# love-flow-lamp.net
KiCad netlist of a schematic drawn in Altium Designer
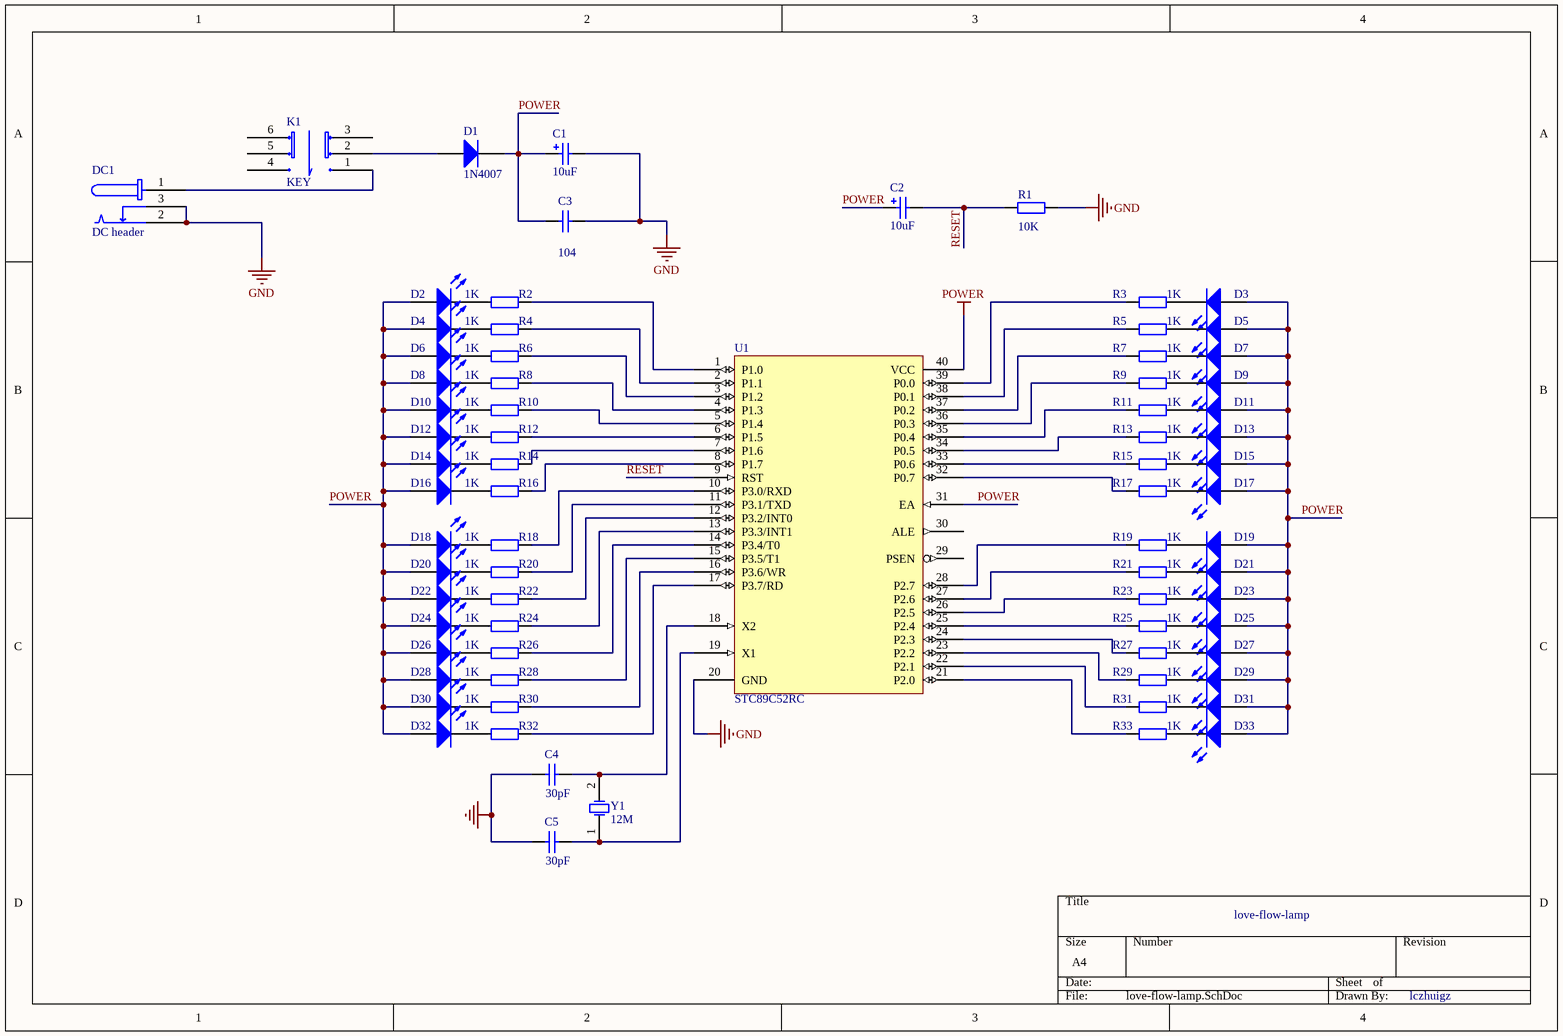
[diagram p0: love-flow-lamp.SchDoc]

(export (version "E")
  (design (tool "Eeschema 10.0.6"))
  (components
    (comp (ref "C1")
      (value "10uF")
      (footprint "RB1")
      (description "Polarized Capacitor (Radial)")
      (fields (field (name "Comment") "Cap Pol1") (field (name "PUBLISHER") "Altium Limited"))
      (libsource (lib "Schlib1") (part "Cap Pol1"))
    )
    (comp (ref "C2")
      (value "10uF")
      (footprint "RB1")
      (description "Polarized Capacitor (Radial)")
      (fields (field (name "Comment") "Cap Pol1") (field (name "PUBLISHER") "Altium Limited"))
      (libsource (lib "Schlib1") (part "Cap Pol1"))
    )
    (comp (ref "C3")
      (value "104")
      (footprint "RAD-0.1")
      (description "Capacitor")
      (fields (field (name "Comment") "Cap") (field (name "PUBLISHER") "Altium Limited"))
      (libsource (lib "Miscellaneous Devices") (part "Cap"))
    )
    (comp (ref "C4")
      (value "30pF")
      (footprint "RAD-0.1")
      (description "Capacitor")
      (fields (field (name "Comment") "Cap") (field (name "PUBLISHER") "Altium Limited"))
      (libsource (lib "Schlib1") (part "Cap"))
    )
    (comp (ref "C5")
      (value "30pF")
      (footprint "RAD-0.1")
      (description "Capacitor")
      (fields (field (name "Comment") "Cap") (field (name "PUBLISHER") "Altium Limited"))
      (libsource (lib "Schlib1") (part "Cap"))
    )
    (comp (ref "D1")
      (value "1N4007")
      (footprint "DIODE-0.4")
      (description "1 Amp General Purpose Rectifier")
      (fields (field (name "PUBLISHER") "Altium Limited"))
      (libsource (lib "Schlib1") (part "Diode 1N4007"))
    )
    (comp (ref "D2")
      (value "LED0")
      (footprint "LED")
      (description "Typical INFRARED GaAs LED")
      (fields (field (name "PUBLISHER") "Altium Limited"))
      (libsource (lib "Schlib1") (part "LED0"))
    )
    (comp (ref "D3")
      (value "LED0")
      (footprint "LED")
      (description "Typical INFRARED GaAs LED")
      (fields (field (name "PUBLISHER") "Altium Limited"))
      (libsource (lib "Schlib1") (part "LED0"))
    )
    (comp (ref "D4")
      (value "LED0")
      (footprint "LED")
      (description "Typical INFRARED GaAs LED")
      (fields (field (name "PUBLISHER") "Altium Limited"))
      (libsource (lib "Schlib1") (part "LED0"))
    )
    (comp (ref "D5")
      (value "LED0")
      (footprint "LED")
      (description "Typical INFRARED GaAs LED")
      (fields (field (name "PUBLISHER") "Altium Limited"))
      (libsource (lib "Schlib1") (part "LED0"))
    )
    (comp (ref "D6")
      (value "LED0")
      (footprint "LED")
      (description "Typical INFRARED GaAs LED")
      (fields (field (name "PUBLISHER") "Altium Limited"))
      (libsource (lib "Schlib1") (part "LED0"))
    )
    (comp (ref "D7")
      (value "LED0")
      (footprint "LED")
      (description "Typical INFRARED GaAs LED")
      (fields (field (name "PUBLISHER") "Altium Limited"))
      (libsource (lib "Schlib1") (part "LED0"))
    )
    (comp (ref "D8")
      (value "LED0")
      (footprint "LED")
      (description "Typical INFRARED GaAs LED")
      (fields (field (name "PUBLISHER") "Altium Limited"))
      (libsource (lib "Schlib1") (part "LED0"))
    )
    (comp (ref "D9")
      (value "LED0")
      (footprint "LED")
      (description "Typical INFRARED GaAs LED")
      (fields (field (name "PUBLISHER") "Altium Limited"))
      (libsource (lib "Schlib1") (part "LED0"))
    )
    (comp (ref "D10")
      (value "LED0")
      (footprint "LED")
      (description "Typical INFRARED GaAs LED")
      (fields (field (name "PUBLISHER") "Altium Limited"))
      (libsource (lib "Schlib1") (part "LED0"))
    )
    (comp (ref "D11")
      (value "LED0")
      (footprint "LED")
      (description "Typical INFRARED GaAs LED")
      (fields (field (name "PUBLISHER") "Altium Limited"))
      (libsource (lib "Schlib1") (part "LED0"))
    )
    (comp (ref "D12")
      (value "LED0")
      (footprint "LED")
      (description "Typical INFRARED GaAs LED")
      (fields (field (name "PUBLISHER") "Altium Limited"))
      (libsource (lib "Schlib1") (part "LED0"))
    )
    (comp (ref "D13")
      (value "LED0")
      (footprint "LED")
      (description "Typical INFRARED GaAs LED")
      (fields (field (name "PUBLISHER") "Altium Limited"))
      (libsource (lib "Schlib1") (part "LED0"))
    )
    (comp (ref "D14")
      (value "LED0")
      (footprint "LED")
      (description "Typical INFRARED GaAs LED")
      (fields (field (name "PUBLISHER") "Altium Limited"))
      (libsource (lib "Schlib1") (part "LED0"))
    )
    (comp (ref "D15")
      (value "LED0")
      (footprint "LED")
      (description "Typical INFRARED GaAs LED")
      (fields (field (name "PUBLISHER") "Altium Limited"))
      (libsource (lib "Schlib1") (part "LED0"))
    )
    (comp (ref "D16")
      (value "LED0")
      (footprint "LED")
      (description "Typical INFRARED GaAs LED")
      (fields (field (name "PUBLISHER") "Altium Limited"))
      (libsource (lib "Schlib1") (part "LED0"))
    )
    (comp (ref "D17")
      (value "LED0")
      (footprint "LED")
      (description "Typical INFRARED GaAs LED")
      (fields (field (name "PUBLISHER") "Altium Limited"))
      (libsource (lib "Schlib1") (part "LED0"))
    )
    (comp (ref "D18")
      (value "LED0")
      (footprint "LED")
      (description "Typical INFRARED GaAs LED")
      (fields (field (name "PUBLISHER") "Altium Limited"))
      (libsource (lib "Schlib1") (part "LED0"))
    )
    (comp (ref "D19")
      (value "LED0")
      (footprint "LED")
      (description "Typical INFRARED GaAs LED")
      (fields (field (name "PUBLISHER") "Altium Limited"))
      (libsource (lib "Schlib1") (part "LED0"))
    )
    (comp (ref "D20")
      (value "LED0")
      (footprint "LED")
      (description "Typical INFRARED GaAs LED")
      (fields (field (name "PUBLISHER") "Altium Limited"))
      (libsource (lib "Schlib1") (part "LED0"))
    )
    (comp (ref "D21")
      (value "LED0")
      (footprint "LED")
      (description "Typical INFRARED GaAs LED")
      (fields (field (name "PUBLISHER") "Altium Limited"))
      (libsource (lib "Schlib1") (part "LED0"))
    )
    (comp (ref "D22")
      (value "LED0")
      (footprint "LED")
      (description "Typical INFRARED GaAs LED")
      (fields (field (name "PUBLISHER") "Altium Limited"))
      (libsource (lib "Schlib1") (part "LED0"))
    )
    (comp (ref "D23")
      (value "LED0")
      (footprint "LED")
      (description "Typical INFRARED GaAs LED")
      (fields (field (name "PUBLISHER") "Altium Limited"))
      (libsource (lib "Schlib1") (part "LED0"))
    )
    (comp (ref "D24")
      (value "LED0")
      (footprint "LED")
      (description "Typical INFRARED GaAs LED")
      (fields (field (name "PUBLISHER") "Altium Limited"))
      (libsource (lib "Schlib1") (part "LED0"))
    )
    (comp (ref "D25")
      (value "LED0")
      (footprint "LED")
      (description "Typical INFRARED GaAs LED")
      (fields (field (name "PUBLISHER") "Altium Limited"))
      (libsource (lib "Schlib1") (part "LED0"))
    )
    (comp (ref "D26")
      (value "LED0")
      (footprint "LED")
      (description "Typical INFRARED GaAs LED")
      (fields (field (name "PUBLISHER") "Altium Limited"))
      (libsource (lib "Schlib1") (part "LED0"))
    )
    (comp (ref "D27")
      (value "LED0")
      (footprint "LED")
      (description "Typical INFRARED GaAs LED")
      (fields (field (name "PUBLISHER") "Altium Limited"))
      (libsource (lib "Schlib1") (part "LED0"))
    )
    (comp (ref "D28")
      (value "LED0")
      (footprint "LED")
      (description "Typical INFRARED GaAs LED")
      (fields (field (name "PUBLISHER") "Altium Limited"))
      (libsource (lib "Schlib1") (part "LED0"))
    )
    (comp (ref "D29")
      (value "LED0")
      (footprint "LED")
      (description "Typical INFRARED GaAs LED")
      (fields (field (name "PUBLISHER") "Altium Limited"))
      (libsource (lib "Schlib1") (part "LED0"))
    )
    (comp (ref "D30")
      (value "LED0")
      (footprint "LED")
      (description "Typical INFRARED GaAs LED")
      (fields (field (name "PUBLISHER") "Altium Limited"))
      (libsource (lib "Schlib1") (part "LED0"))
    )
    (comp (ref "D31")
      (value "LED0")
      (footprint "LED")
      (description "Typical INFRARED GaAs LED")
      (fields (field (name "PUBLISHER") "Altium Limited"))
      (libsource (lib "Schlib1") (part "LED0"))
    )
    (comp (ref "D32")
      (value "LED0")
      (footprint "LED")
      (description "Typical INFRARED GaAs LED")
      (fields (field (name "PUBLISHER") "Altium Limited"))
      (libsource (lib "Schlib1") (part "LED0"))
    )
    (comp (ref "D33")
      (value "LED0")
      (footprint "LED")
      (description "Typical INFRARED GaAs LED")
      (fields (field (name "PUBLISHER") "Altium Limited"))
      (libsource (lib "Schlib1") (part "LED0"))
    )
    (comp (ref "DC1") (value "DC header") (footprint "DC") (libsource (lib "love-flow-lamp") (part "DC")))
    (comp (ref "K1") (value "KEY") (footprint "KEY-6") (libsource (lib "love-flow-lamp") (part "KEY")))
    (comp (ref "R1")
      (value "10K")
      (footprint "AXIAL-0.3")
      (description "Resistor")
      (fields (field (name "Comment") "Res2") (field (name "PUBLISHER") "Altium Limited"))
      (libsource (lib "Schlib1") (part "Res2"))
    )
    (comp (ref "R2")
      (value "1K")
      (footprint "AXIAL-0.3")
      (description "Resistor")
      (fields (field (name "Comment") "Res2") (field (name "PUBLISHER") "Altium Limited"))
      (libsource (lib "Schlib1") (part "Res2"))
    )
    (comp (ref "R3")
      (value "1K")
      (footprint "AXIAL-0.3")
      (description "Resistor")
      (fields (field (name "Comment") "Res2") (field (name "PUBLISHER") "Altium Limited"))
      (libsource (lib "Schlib1") (part "Res2"))
    )
    (comp (ref "R4")
      (value "1K")
      (footprint "AXIAL-0.3")
      (description "Resistor")
      (fields (field (name "Comment") "Res2") (field (name "PUBLISHER") "Altium Limited"))
      (libsource (lib "Schlib1") (part "Res2"))
    )
    (comp (ref "R5")
      (value "1K")
      (footprint "AXIAL-0.3")
      (description "Resistor")
      (fields (field (name "Comment") "Res2") (field (name "PUBLISHER") "Altium Limited"))
      (libsource (lib "Schlib1") (part "Res2"))
    )
    (comp (ref "R6")
      (value "1K")
      (footprint "AXIAL-0.3")
      (description "Resistor")
      (fields (field (name "Comment") "Res2") (field (name "PUBLISHER") "Altium Limited"))
      (libsource (lib "Schlib1") (part "Res2"))
    )
    (comp (ref "R7")
      (value "1K")
      (footprint "AXIAL-0.3")
      (description "Resistor")
      (fields (field (name "Comment") "Res2") (field (name "PUBLISHER") "Altium Limited"))
      (libsource (lib "Schlib1") (part "Res2"))
    )
    (comp (ref "R8")
      (value "1K")
      (footprint "AXIAL-0.3")
      (description "Resistor")
      (fields (field (name "Comment") "Res2") (field (name "PUBLISHER") "Altium Limited"))
      (libsource (lib "Schlib1") (part "Res2"))
    )
    (comp (ref "R9")
      (value "1K")
      (footprint "AXIAL-0.3")
      (description "Resistor")
      (fields (field (name "Comment") "Res2") (field (name "PUBLISHER") "Altium Limited"))
      (libsource (lib "Schlib1") (part "Res2"))
    )
    (comp (ref "R10")
      (value "1K")
      (footprint "AXIAL-0.3")
      (description "Resistor")
      (fields (field (name "Comment") "Res2") (field (name "PUBLISHER") "Altium Limited"))
      (libsource (lib "Schlib1") (part "Res2"))
    )
    (comp (ref "R11")
      (value "1K")
      (footprint "AXIAL-0.3")
      (description "Resistor")
      (fields (field (name "Comment") "Res2") (field (name "PUBLISHER") "Altium Limited"))
      (libsource (lib "Schlib1") (part "Res2"))
    )
    (comp (ref "R12")
      (value "1K")
      (footprint "AXIAL-0.3")
      (description "Resistor")
      (fields (field (name "Comment") "Res2") (field (name "PUBLISHER") "Altium Limited"))
      (libsource (lib "Schlib1") (part "Res2"))
    )
    (comp (ref "R13")
      (value "1K")
      (footprint "AXIAL-0.3")
      (description "Resistor")
      (fields (field (name "Comment") "Res2") (field (name "PUBLISHER") "Altium Limited"))
      (libsource (lib "Schlib1") (part "Res2"))
    )
    (comp (ref "R14")
      (value "1K")
      (footprint "AXIAL-0.3")
      (description "Resistor")
      (fields (field (name "Comment") "Res2") (field (name "PUBLISHER") "Altium Limited"))
      (libsource (lib "Schlib1") (part "Res2"))
    )
    (comp (ref "R15")
      (value "1K")
      (footprint "AXIAL-0.3")
      (description "Resistor")
      (fields (field (name "Comment") "Res2") (field (name "PUBLISHER") "Altium Limited"))
      (libsource (lib "Schlib1") (part "Res2"))
    )
    (comp (ref "R16")
      (value "1K")
      (footprint "AXIAL-0.3")
      (description "Resistor")
      (fields (field (name "Comment") "Res2") (field (name "PUBLISHER") "Altium Limited"))
      (libsource (lib "Schlib1") (part "Res2"))
    )
    (comp (ref "R17")
      (value "1K")
      (footprint "AXIAL-0.3")
      (description "Resistor")
      (fields (field (name "Comment") "Res2") (field (name "PUBLISHER") "Altium Limited"))
      (libsource (lib "Schlib1") (part "Res2"))
    )
    (comp (ref "R18")
      (value "1K")
      (footprint "AXIAL-0.3")
      (description "Resistor")
      (fields (field (name "Comment") "Res2") (field (name "PUBLISHER") "Altium Limited"))
      (libsource (lib "Schlib1") (part "Res2"))
    )
    (comp (ref "R19")
      (value "1K")
      (footprint "AXIAL-0.3")
      (description "Resistor")
      (fields (field (name "Comment") "Res2") (field (name "PUBLISHER") "Altium Limited"))
      (libsource (lib "Schlib1") (part "Res2"))
    )
    (comp (ref "R20")
      (value "1K")
      (footprint "AXIAL-0.3")
      (description "Resistor")
      (fields (field (name "Comment") "Res2") (field (name "PUBLISHER") "Altium Limited"))
      (libsource (lib "Schlib1") (part "Res2"))
    )
    (comp (ref "R21")
      (value "1K")
      (footprint "AXIAL-0.3")
      (description "Resistor")
      (fields (field (name "Comment") "Res2") (field (name "PUBLISHER") "Altium Limited"))
      (libsource (lib "Schlib1") (part "Res2"))
    )
    (comp (ref "R22")
      (value "1K")
      (footprint "AXIAL-0.3")
      (description "Resistor")
      (fields (field (name "Comment") "Res2") (field (name "PUBLISHER") "Altium Limited"))
      (libsource (lib "Schlib1") (part "Res2"))
    )
    (comp (ref "R23")
      (value "1K")
      (footprint "AXIAL-0.3")
      (description "Resistor")
      (fields (field (name "Comment") "Res2") (field (name "PUBLISHER") "Altium Limited"))
      (libsource (lib "Schlib1") (part "Res2"))
    )
    (comp (ref "R24")
      (value "1K")
      (footprint "AXIAL-0.3")
      (description "Resistor")
      (fields (field (name "Comment") "Res2") (field (name "PUBLISHER") "Altium Limited"))
      (libsource (lib "Schlib1") (part "Res2"))
    )
    (comp (ref "R25")
      (value "1K")
      (footprint "AXIAL-0.3")
      (description "Resistor")
      (fields (field (name "Comment") "Res2") (field (name "PUBLISHER") "Altium Limited"))
      (libsource (lib "Schlib1") (part "Res2"))
    )
    (comp (ref "R26")
      (value "1K")
      (footprint "AXIAL-0.3")
      (description "Resistor")
      (fields (field (name "Comment") "Res2") (field (name "PUBLISHER") "Altium Limited"))
      (libsource (lib "Schlib1") (part "Res2"))
    )
    (comp (ref "R27")
      (value "1K")
      (footprint "AXIAL-0.3")
      (description "Resistor")
      (fields (field (name "Comment") "Res2") (field (name "PUBLISHER") "Altium Limited"))
      (libsource (lib "Schlib1") (part "Res2"))
    )
    (comp (ref "R28")
      (value "1K")
      (footprint "AXIAL-0.3")
      (description "Resistor")
      (fields (field (name "Comment") "Res2") (field (name "PUBLISHER") "Altium Limited"))
      (libsource (lib "Schlib1") (part "Res2"))
    )
    (comp (ref "R29")
      (value "1K")
      (footprint "AXIAL-0.3")
      (description "Resistor")
      (fields (field (name "Comment") "Res2") (field (name "PUBLISHER") "Altium Limited"))
      (libsource (lib "Schlib1") (part "Res2"))
    )
    (comp (ref "R30")
      (value "1K")
      (footprint "AXIAL-0.3")
      (description "Resistor")
      (fields (field (name "Comment") "Res2") (field (name "PUBLISHER") "Altium Limited"))
      (libsource (lib "Schlib1") (part "Res2"))
    )
    (comp (ref "R31")
      (value "1K")
      (footprint "AXIAL-0.3")
      (description "Resistor")
      (fields (field (name "Comment") "Res2") (field (name "PUBLISHER") "Altium Limited"))
      (libsource (lib "Schlib1") (part "Res2"))
    )
    (comp (ref "R32")
      (value "1K")
      (footprint "AXIAL-0.3")
      (description "Resistor")
      (fields (field (name "Comment") "Res2") (field (name "PUBLISHER") "Altium Limited"))
      (libsource (lib "Schlib1") (part "Res2"))
    )
    (comp (ref "R33")
      (value "1K")
      (footprint "AXIAL-0.3")
      (description "Resistor")
      (fields (field (name "Comment") "Res2") (field (name "PUBLISHER") "Altium Limited"))
      (libsource (lib "Schlib1") (part "Res2"))
    )
    (comp (ref "U1")
      (value "STC89C52RC")
      (footprint "PDIP-40")
      (libsource (lib "Schlib1") (part "STC89C52RC"))
    )
    (comp (ref "Y1")
      (value "12M")
      (footprint "BCY-W2/E4.7")
      (description "Crystal Oscillator")
      (fields (field (name "PUBLISHER") "Altium Limited"))
      (libsource (lib "Schlib1") (part "XTAL"))
    )
  )
  (nets
    (net (code "1") (name "/RESET") (class "Default")
      (node (ref "C2") (pin "2") (pinfunction "2_2") (pintype "passive"))
      (node (ref "R1") (pin "1") (pinfunction "1_1") (pintype "passive"))
      (node (ref "U1") (pin "9") (pinfunction "RST_9") (pintype "input"))
    )
    (net (code "2") (name "GND") (class "Default")
      (node (ref "C1") (pin "2") (pinfunction "2_2") (pintype "passive"))
      (node (ref "C3") (pin "2") (pinfunction "2_2") (pintype "passive"))
      (node (ref "C4") (pin "1") (pinfunction "1_1") (pintype "passive"))
      (node (ref "C5") (pin "1") (pinfunction "1_1") (pintype "passive"))
      (node (ref "DC1") (pin "2") (pinfunction "2_2") (pintype "passive"))
      (node (ref "DC1") (pin "3") (pinfunction "3_3") (pintype "passive"))
      (node (ref "R1") (pin "2") (pinfunction "2_2") (pintype "passive"))
      (node (ref "U1") (pin "20") (pinfunction "GND_20") (pintype "power_in"))
    )
    (net (code "3") (name "Net-(D1-A)") (class "Default")
      (node (ref "D1") (pin "1") (pinfunction "A_1") (pintype "passive"))
      (node (ref "K1") (pin "2") (pinfunction "2_2") (pintype "passive"))
    )
    (net (code "4") (name "Net-(D2-K)") (class "Default")
      (node (ref "D2") (pin "2") (pinfunction "K_2") (pintype "passive"))
      (node (ref "R2") (pin "1") (pinfunction "1_1") (pintype "passive"))
    )
    (net (code "5") (name "Net-(D3-K)") (class "Default")
      (node (ref "D3") (pin "2") (pinfunction "K_2") (pintype "passive"))
      (node (ref "R3") (pin "2") (pinfunction "2_2") (pintype "passive"))
    )
    (net (code "6") (name "Net-(D4-K)") (class "Default")
      (node (ref "D4") (pin "2") (pinfunction "K_2") (pintype "passive"))
      (node (ref "R4") (pin "1") (pinfunction "1_1") (pintype "passive"))
    )
    (net (code "7") (name "Net-(D5-K)") (class "Default")
      (node (ref "D5") (pin "2") (pinfunction "K_2") (pintype "passive"))
      (node (ref "R5") (pin "2") (pinfunction "2_2") (pintype "passive"))
    )
    (net (code "8") (name "Net-(D6-K)") (class "Default")
      (node (ref "D6") (pin "2") (pinfunction "K_2") (pintype "passive"))
      (node (ref "R6") (pin "1") (pinfunction "1_1") (pintype "passive"))
    )
    (net (code "9") (name "Net-(D7-K)") (class "Default")
      (node (ref "D7") (pin "2") (pinfunction "K_2") (pintype "passive"))
      (node (ref "R7") (pin "2") (pinfunction "2_2") (pintype "passive"))
    )
    (net (code "10") (name "Net-(D8-K)") (class "Default")
      (node (ref "D8") (pin "2") (pinfunction "K_2") (pintype "passive"))
      (node (ref "R8") (pin "1") (pinfunction "1_1") (pintype "passive"))
    )
    (net (code "11") (name "Net-(D9-K)") (class "Default")
      (node (ref "D9") (pin "2") (pinfunction "K_2") (pintype "passive"))
      (node (ref "R9") (pin "2") (pinfunction "2_2") (pintype "passive"))
    )
    (net (code "12") (name "Net-(D10-K)") (class "Default")
      (node (ref "D10") (pin "2") (pinfunction "K_2") (pintype "passive"))
      (node (ref "R10") (pin "1") (pinfunction "1_1") (pintype "passive"))
    )
    (net (code "13") (name "Net-(D11-K)") (class "Default")
      (node (ref "D11") (pin "2") (pinfunction "K_2") (pintype "passive"))
      (node (ref "R11") (pin "2") (pinfunction "2_2") (pintype "passive"))
    )
    (net (code "14") (name "Net-(D12-K)") (class "Default")
      (node (ref "D12") (pin "2") (pinfunction "K_2") (pintype "passive"))
      (node (ref "R12") (pin "1") (pinfunction "1_1") (pintype "passive"))
    )
    (net (code "15") (name "Net-(D13-K)") (class "Default")
      (node (ref "D13") (pin "2") (pinfunction "K_2") (pintype "passive"))
      (node (ref "R13") (pin "2") (pinfunction "2_2") (pintype "passive"))
    )
    (net (code "16") (name "Net-(D14-K)") (class "Default")
      (node (ref "D14") (pin "2") (pinfunction "K_2") (pintype "passive"))
      (node (ref "R14") (pin "1") (pinfunction "1_1") (pintype "passive"))
    )
    (net (code "17") (name "Net-(D15-K)") (class "Default")
      (node (ref "D15") (pin "2") (pinfunction "K_2") (pintype "passive"))
      (node (ref "R15") (pin "2") (pinfunction "2_2") (pintype "passive"))
    )
    (net (code "18") (name "Net-(D16-K)") (class "Default")
      (node (ref "D16") (pin "2") (pinfunction "K_2") (pintype "passive"))
      (node (ref "R16") (pin "1") (pinfunction "1_1") (pintype "passive"))
    )
    (net (code "19") (name "Net-(D17-K)") (class "Default")
      (node (ref "D17") (pin "2") (pinfunction "K_2") (pintype "passive"))
      (node (ref "R17") (pin "2") (pinfunction "2_2") (pintype "passive"))
    )
    (net (code "20") (name "Net-(D18-K)") (class "Default")
      (node (ref "D18") (pin "2") (pinfunction "K_2") (pintype "passive"))
      (node (ref "R18") (pin "1") (pinfunction "1_1") (pintype "passive"))
    )
    (net (code "21") (name "Net-(D19-K)") (class "Default")
      (node (ref "D19") (pin "2") (pinfunction "K_2") (pintype "passive"))
      (node (ref "R19") (pin "2") (pinfunction "2_2") (pintype "passive"))
    )
    (net (code "22") (name "Net-(D20-K)") (class "Default")
      (node (ref "D20") (pin "2") (pinfunction "K_2") (pintype "passive"))
      (node (ref "R20") (pin "1") (pinfunction "1_1") (pintype "passive"))
    )
    (net (code "23") (name "Net-(D21-K)") (class "Default")
      (node (ref "D21") (pin "2") (pinfunction "K_2") (pintype "passive"))
      (node (ref "R21") (pin "2") (pinfunction "2_2") (pintype "passive"))
    )
    (net (code "24") (name "Net-(D22-K)") (class "Default")
      (node (ref "D22") (pin "2") (pinfunction "K_2") (pintype "passive"))
      (node (ref "R22") (pin "1") (pinfunction "1_1") (pintype "passive"))
    )
    (net (code "25") (name "Net-(D23-K)") (class "Default")
      (node (ref "D23") (pin "2") (pinfunction "K_2") (pintype "passive"))
      (node (ref "R23") (pin "2") (pinfunction "2_2") (pintype "passive"))
    )
    (net (code "26") (name "Net-(D24-K)") (class "Default")
      (node (ref "D24") (pin "2") (pinfunction "K_2") (pintype "passive"))
      (node (ref "R24") (pin "1") (pinfunction "1_1") (pintype "passive"))
    )
    (net (code "27") (name "Net-(D25-K)") (class "Default")
      (node (ref "D25") (pin "2") (pinfunction "K_2") (pintype "passive"))
      (node (ref "R25") (pin "2") (pinfunction "2_2") (pintype "passive"))
    )
    (net (code "28") (name "Net-(D26-K)") (class "Default")
      (node (ref "D26") (pin "2") (pinfunction "K_2") (pintype "passive"))
      (node (ref "R26") (pin "1") (pinfunction "1_1") (pintype "passive"))
    )
    (net (code "29") (name "Net-(D27-K)") (class "Default")
      (node (ref "D27") (pin "2") (pinfunction "K_2") (pintype "passive"))
      (node (ref "R27") (pin "2") (pinfunction "2_2") (pintype "passive"))
    )
    (net (code "30") (name "Net-(D28-K)") (class "Default")
      (node (ref "D28") (pin "2") (pinfunction "K_2") (pintype "passive"))
      (node (ref "R28") (pin "1") (pinfunction "1_1") (pintype "passive"))
    )
    (net (code "31") (name "Net-(D29-K)") (class "Default")
      (node (ref "D29") (pin "2") (pinfunction "K_2") (pintype "passive"))
      (node (ref "R29") (pin "2") (pinfunction "2_2") (pintype "passive"))
    )
    (net (code "32") (name "Net-(D30-K)") (class "Default")
      (node (ref "D30") (pin "2") (pinfunction "K_2") (pintype "passive"))
      (node (ref "R30") (pin "1") (pinfunction "1_1") (pintype "passive"))
    )
    (net (code "33") (name "Net-(D31-K)") (class "Default")
      (node (ref "D31") (pin "2") (pinfunction "K_2") (pintype "passive"))
      (node (ref "R31") (pin "2") (pinfunction "2_2") (pintype "passive"))
    )
    (net (code "34") (name "Net-(D32-K)") (class "Default")
      (node (ref "D32") (pin "2") (pinfunction "K_2") (pintype "passive"))
      (node (ref "R32") (pin "1") (pinfunction "1_1") (pintype "passive"))
    )
    (net (code "35") (name "Net-(D33-K)") (class "Default")
      (node (ref "D33") (pin "2") (pinfunction "K_2") (pintype "passive"))
      (node (ref "R33") (pin "2") (pinfunction "2_2") (pintype "passive"))
    )
    (net (code "36") (name "Net-(DC1-Pad1)") (class "Default")
      (node (ref "DC1") (pin "1") (pinfunction "1_1") (pintype "passive"))
      (node (ref "K1") (pin "1") (pinfunction "1_1") (pintype "passive"))
    )
    (net (code "37") (name "Net-(U1-P0.0)") (class "Default")
      (node (ref "R3") (pin "1") (pinfunction "1_1") (pintype "passive"))
      (node (ref "U1") (pin "39") (pinfunction "P0.0_39") (pintype "bidirectional"))
    )
    (net (code "38") (name "Net-(U1-P0.1)") (class "Default")
      (node (ref "R5") (pin "1") (pinfunction "1_1") (pintype "passive"))
      (node (ref "U1") (pin "38") (pinfunction "P0.1_38") (pintype "bidirectional"))
    )
    (net (code "39") (name "Net-(U1-P0.2)") (class "Default")
      (node (ref "R7") (pin "1") (pinfunction "1_1") (pintype "passive"))
      (node (ref "U1") (pin "37") (pinfunction "P0.2_37") (pintype "bidirectional"))
    )
    (net (code "40") (name "Net-(U1-P0.3)") (class "Default")
      (node (ref "R9") (pin "1") (pinfunction "1_1") (pintype "passive"))
      (node (ref "U1") (pin "36") (pinfunction "P0.3_36") (pintype "bidirectional"))
    )
    (net (code "41") (name "Net-(U1-P0.4)") (class "Default")
      (node (ref "R11") (pin "1") (pinfunction "1_1") (pintype "passive"))
      (node (ref "U1") (pin "35") (pinfunction "P0.4_35") (pintype "bidirectional"))
    )
    (net (code "42") (name "Net-(U1-P0.5)") (class "Default")
      (node (ref "R13") (pin "1") (pinfunction "1_1") (pintype "passive"))
      (node (ref "U1") (pin "34") (pinfunction "P0.5_34") (pintype "bidirectional"))
    )
    (net (code "43") (name "Net-(U1-P0.6)") (class "Default")
      (node (ref "R15") (pin "1") (pinfunction "1_1") (pintype "passive"))
      (node (ref "U1") (pin "33") (pinfunction "P0.6_33") (pintype "bidirectional"))
    )
    (net (code "44") (name "Net-(U1-P0.7)") (class "Default")
      (node (ref "R17") (pin "1") (pinfunction "1_1") (pintype "passive"))
      (node (ref "U1") (pin "32") (pinfunction "P0.7_32") (pintype "bidirectional"))
    )
    (net (code "45") (name "Net-(U1-P1.0)") (class "Default")
      (node (ref "R2") (pin "2") (pinfunction "2_2") (pintype "passive"))
      (node (ref "U1") (pin "1") (pinfunction "P1.0_1") (pintype "bidirectional"))
    )
    (net (code "46") (name "Net-(U1-P1.1)") (class "Default")
      (node (ref "R4") (pin "2") (pinfunction "2_2") (pintype "passive"))
      (node (ref "U1") (pin "2") (pinfunction "P1.1_2") (pintype "bidirectional"))
    )
    (net (code "47") (name "Net-(U1-P1.2)") (class "Default")
      (node (ref "R6") (pin "2") (pinfunction "2_2") (pintype "passive"))
      (node (ref "U1") (pin "3") (pinfunction "P1.2_3") (pintype "bidirectional"))
    )
    (net (code "48") (name "Net-(U1-P1.3)") (class "Default")
      (node (ref "R8") (pin "2") (pinfunction "2_2") (pintype "passive"))
      (node (ref "U1") (pin "4") (pinfunction "P1.3_4") (pintype "bidirectional"))
    )
    (net (code "49") (name "Net-(U1-P1.4)") (class "Default")
      (node (ref "R10") (pin "2") (pinfunction "2_2") (pintype "passive"))
      (node (ref "U1") (pin "5") (pinfunction "P1.4_5") (pintype "bidirectional"))
    )
    (net (code "50") (name "Net-(U1-P1.5)") (class "Default")
      (node (ref "R12") (pin "2") (pinfunction "2_2") (pintype "passive"))
      (node (ref "U1") (pin "6") (pinfunction "P1.5_6") (pintype "bidirectional"))
    )
    (net (code "51") (name "Net-(U1-P1.6)") (class "Default")
      (node (ref "R14") (pin "2") (pinfunction "2_2") (pintype "passive"))
      (node (ref "U1") (pin "7") (pinfunction "P1.6_7") (pintype "bidirectional"))
    )
    (net (code "52") (name "Net-(U1-P1.7)") (class "Default")
      (node (ref "R16") (pin "2") (pinfunction "2_2") (pintype "passive"))
      (node (ref "U1") (pin "8") (pinfunction "P1.7_8") (pintype "bidirectional"))
    )
    (net (code "53") (name "Net-(U1-P2.0)") (class "Default")
      (node (ref "R33") (pin "1") (pinfunction "1_1") (pintype "passive"))
      (node (ref "U1") (pin "21") (pinfunction "P2.0_21") (pintype "bidirectional"))
    )
    (net (code "54") (name "Net-(U1-P2.1)") (class "Default")
      (node (ref "R31") (pin "1") (pinfunction "1_1") (pintype "passive"))
      (node (ref "U1") (pin "22") (pinfunction "P2.1_22") (pintype "bidirectional"))
    )
    (net (code "55") (name "Net-(U1-P2.2)") (class "Default")
      (node (ref "R29") (pin "1") (pinfunction "1_1") (pintype "passive"))
      (node (ref "U1") (pin "23") (pinfunction "P2.2_23") (pintype "bidirectional"))
    )
    (net (code "56") (name "Net-(U1-P2.3)") (class "Default")
      (node (ref "R27") (pin "1") (pinfunction "1_1") (pintype "passive"))
      (node (ref "U1") (pin "24") (pinfunction "P2.3_24") (pintype "bidirectional"))
    )
    (net (code "57") (name "Net-(U1-P2.4)") (class "Default")
      (node (ref "R25") (pin "1") (pinfunction "1_1") (pintype "passive"))
      (node (ref "U1") (pin "25") (pinfunction "P2.4_25") (pintype "bidirectional"))
    )
    (net (code "58") (name "Net-(U1-P2.5)") (class "Default")
      (node (ref "R23") (pin "1") (pinfunction "1_1") (pintype "passive"))
      (node (ref "U1") (pin "26") (pinfunction "P2.5_26") (pintype "bidirectional"))
    )
    (net (code "59") (name "Net-(U1-P2.6)") (class "Default")
      (node (ref "R21") (pin "1") (pinfunction "1_1") (pintype "passive"))
      (node (ref "U1") (pin "27") (pinfunction "P2.6_27") (pintype "bidirectional"))
    )
    (net (code "60") (name "Net-(U1-P2.7)") (class "Default")
      (node (ref "R19") (pin "1") (pinfunction "1_1") (pintype "passive"))
      (node (ref "U1") (pin "28") (pinfunction "P2.7_28") (pintype "bidirectional"))
    )
    (net (code "61") (name "Net-(U1-P3.0{slash}RXD)") (class "Default")
      (node (ref "R18") (pin "2") (pinfunction "2_2") (pintype "passive"))
      (node (ref "U1") (pin "10") (pinfunction "P3.0/RXD_10") (pintype "bidirectional"))
    )
    (net (code "62") (name "Net-(U1-P3.1{slash}TXD)") (class "Default")
      (node (ref "R20") (pin "2") (pinfunction "2_2") (pintype "passive"))
      (node (ref "U1") (pin "11") (pinfunction "P3.1/TXD_11") (pintype "bidirectional"))
    )
    (net (code "63") (name "Net-(U1-P3.2{slash}INT0)") (class "Default")
      (node (ref "R22") (pin "2") (pinfunction "2_2") (pintype "passive"))
      (node (ref "U1") (pin "12") (pinfunction "P3.2/INT0_12") (pintype "bidirectional"))
    )
    (net (code "64") (name "Net-(U1-P3.3{slash}INT1)") (class "Default")
      (node (ref "R24") (pin "2") (pinfunction "2_2") (pintype "passive"))
      (node (ref "U1") (pin "13") (pinfunction "P3.3/INT1_13") (pintype "bidirectional"))
    )
    (net (code "65") (name "Net-(U1-P3.4{slash}T0)") (class "Default")
      (node (ref "R26") (pin "2") (pinfunction "2_2") (pintype "passive"))
      (node (ref "U1") (pin "14") (pinfunction "P3.4/T0_14") (pintype "bidirectional"))
    )
    (net (code "66") (name "Net-(U1-P3.5{slash}T1)") (class "Default")
      (node (ref "R28") (pin "2") (pinfunction "2_2") (pintype "passive"))
      (node (ref "U1") (pin "15") (pinfunction "P3.5/T1_15") (pintype "bidirectional"))
    )
    (net (code "67") (name "Net-(U1-P3.6{slash}WR)") (class "Default")
      (node (ref "R30") (pin "2") (pinfunction "2_2") (pintype "passive"))
      (node (ref "U1") (pin "16") (pinfunction "P3.6/WR_16") (pintype "bidirectional"))
    )
    (net (code "68") (name "Net-(U1-P3.7{slash}RD)") (class "Default")
      (node (ref "R32") (pin "2") (pinfunction "2_2") (pintype "passive"))
      (node (ref "U1") (pin "17") (pinfunction "P3.7/RD_17") (pintype "bidirectional"))
    )
    (net (code "69") (name "Net-(U1-X1)") (class "Default")
      (node (ref "C5") (pin "2") (pinfunction "2_2") (pintype "passive"))
      (node (ref "U1") (pin "19") (pinfunction "X1_19") (pintype "input"))
      (node (ref "Y1") (pin "1") (pinfunction "OSC1_1") (pintype "passive"))
    )
    (net (code "70") (name "Net-(U1-X2)") (class "Default")
      (node (ref "C4") (pin "2") (pinfunction "2_2") (pintype "passive"))
      (node (ref "U1") (pin "18") (pinfunction "X2_18") (pintype "input"))
      (node (ref "Y1") (pin "2") (pinfunction "OSC2_2") (pintype "passive"))
    )
    (net (code "71") (name "POWER") (class "Default")
      (node (ref "C1") (pin "1") (pinfunction "1_1") (pintype "passive"))
      (node (ref "C2") (pin "1") (pinfunction "1_1") (pintype "passive"))
      (node (ref "C3") (pin "1") (pinfunction "1_1") (pintype "passive"))
      (node (ref "D1") (pin "2") (pinfunction "K_2") (pintype "passive"))
      (node (ref "D10") (pin "1") (pinfunction "A_1") (pintype "passive"))
      (node (ref "D11") (pin "1") (pinfunction "A_1") (pintype "passive"))
      (node (ref "D12") (pin "1") (pinfunction "A_1") (pintype "passive"))
      (node (ref "D13") (pin "1") (pinfunction "A_1") (pintype "passive"))
      (node (ref "D14") (pin "1") (pinfunction "A_1") (pintype "passive"))
      (node (ref "D15") (pin "1") (pinfunction "A_1") (pintype "passive"))
      (node (ref "D16") (pin "1") (pinfunction "A_1") (pintype "passive"))
      (node (ref "D17") (pin "1") (pinfunction "A_1") (pintype "passive"))
      (node (ref "D18") (pin "1") (pinfunction "A_1") (pintype "passive"))
      (node (ref "D19") (pin "1") (pinfunction "A_1") (pintype "passive"))
      (node (ref "D2") (pin "1") (pinfunction "A_1") (pintype "passive"))
      (node (ref "D20") (pin "1") (pinfunction "A_1") (pintype "passive"))
      (node (ref "D21") (pin "1") (pinfunction "A_1") (pintype "passive"))
      (node (ref "D22") (pin "1") (pinfunction "A_1") (pintype "passive"))
      (node (ref "D23") (pin "1") (pinfunction "A_1") (pintype "passive"))
      (node (ref "D24") (pin "1") (pinfunction "A_1") (pintype "passive"))
      (node (ref "D25") (pin "1") (pinfunction "A_1") (pintype "passive"))
      (node (ref "D26") (pin "1") (pinfunction "A_1") (pintype "passive"))
      (node (ref "D27") (pin "1") (pinfunction "A_1") (pintype "passive"))
      (node (ref "D28") (pin "1") (pinfunction "A_1") (pintype "passive"))
      (node (ref "D29") (pin "1") (pinfunction "A_1") (pintype "passive"))
      (node (ref "D3") (pin "1") (pinfunction "A_1") (pintype "passive"))
      (node (ref "D30") (pin "1") (pinfunction "A_1") (pintype "passive"))
      (node (ref "D31") (pin "1") (pinfunction "A_1") (pintype "passive"))
      (node (ref "D32") (pin "1") (pinfunction "A_1") (pintype "passive"))
      (node (ref "D33") (pin "1") (pinfunction "A_1") (pintype "passive"))
      (node (ref "D4") (pin "1") (pinfunction "A_1") (pintype "passive"))
      (node (ref "D5") (pin "1") (pinfunction "A_1") (pintype "passive"))
      (node (ref "D6") (pin "1") (pinfunction "A_1") (pintype "passive"))
      (node (ref "D7") (pin "1") (pinfunction "A_1") (pintype "passive"))
      (node (ref "D8") (pin "1") (pinfunction "A_1") (pintype "passive"))
      (node (ref "D9") (pin "1") (pinfunction "A_1") (pintype "passive"))
      (node (ref "U1") (pin "31") (pinfunction "EA_31") (pintype "input"))
      (node (ref "U1") (pin "40") (pinfunction "VCC_40") (pintype "power_in"))
    )
    (net (code "72") (name "unconnected-(K1-Pad3)") (class "Default")
      (node (ref "K1") (pin "3") (pinfunction "3_3") (pintype "passive"))
    )
    (net (code "73") (name "unconnected-(K1-Pad4)") (class "Default")
      (node (ref "K1") (pin "4") (pinfunction "4_4") (pintype "passive"))
    )
    (net (code "74") (name "unconnected-(K1-Pad5)") (class "Default")
      (node (ref "K1") (pin "5") (pinfunction "5_5") (pintype "passive"))
    )
    (net (code "75") (name "unconnected-(K1-Pad6)") (class "Default")
      (node (ref "K1") (pin "6") (pinfunction "6_6") (pintype "passive"))
    )
    (net (code "76") (name "unconnected-(U1-ALE-Pad30)") (class "Default")
      (node (ref "U1") (pin "30") (pinfunction "ALE_30") (pintype "output"))
    )
    (net (code "77") (name "unconnected-(U1-PSEN-Pad29)") (class "Default")
      (node (ref "U1") (pin "29") (pinfunction "PSEN_29") (pintype "output"))
    )
  )
)
